# ind_pwm_gen.net
KiCad netlist of a schematic drawn in EAGLE
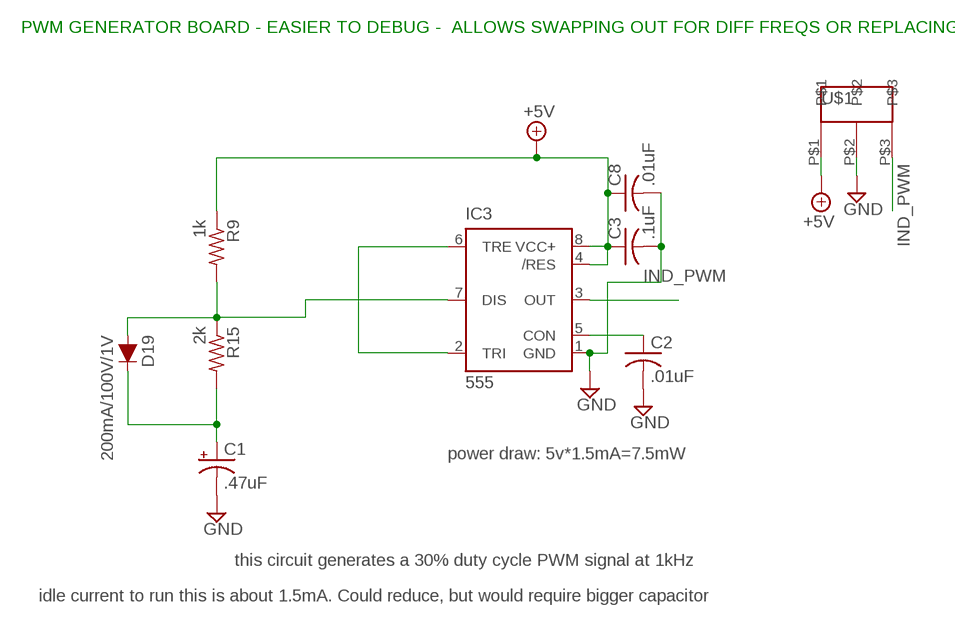
[diagram p0: schematic, sheet 1]

(export (version "E")
  (design (tool "Eeschema 10.0.6"))
  (components
    (comp (ref "C1")
      (value ".47uF")
      (footprint "eagle-import:E2-4")
      (libsource (lib "eagle-import") (part "CPOL-USE2-4"))
    )
    (comp (ref "C2")
      (value ".01uF")
      (footprint "eagle-import:C025-030X050")
      (libsource (lib "eagle-import") (part "C-US025-030X050"))
    )
    (comp (ref "C3")
      (value ".1uF")
      (footprint "eagle-import:C025-030X050")
      (libsource (lib "eagle-import") (part "C-US025-030X050"))
    )
    (comp (ref "C8")
      (value ".01uF")
      (footprint "eagle-import:C025-030X050")
      (libsource (lib "eagle-import") (part "C-US025-030X050"))
    )
    (comp (ref "D19")
      (value "200mA/100V/1V")
      (footprint "eagle-import:DIODE-1N4148")
      (libsource (lib "eagle-import") (part "DIODE-1N4148"))
    )
    (comp (ref "IC3")
      (value "555")
      (footprint "eagle-import:DIP08")
      (libsource (lib "eagle-import") (part "555P"))
    )
    (comp (ref "R9")
      (value "1k")
      (footprint "eagle-import:0204_7")
      (libsource (lib "eagle-import") (part "R-US_0204/7"))
    )
    (comp (ref "R15")
      (value "2k")
      (footprint "eagle-import:0204_7")
      (libsource (lib "eagle-import") (part "R-US_0204/7"))
    )
    (comp (ref "U$1")
      (value "3-PIN-HEADER")
      (footprint "eagle-import:3-PIN-HEADER")
      (libsource (lib "eagle-import") (part "3-PIN-HEADER"))
    )
  )
  (nets
    (net (code "1") (name "+5V") (class "Default")
      (node (ref "C3") (pin "1") (pinfunction "1_1") (pintype "passive"))
      (node (ref "C8") (pin "1") (pinfunction "1_1") (pintype "passive"))
      (node (ref "IC3") (pin "4") (pinfunction "/RES_4") (pintype "input"))
      (node (ref "IC3") (pin "8") (pinfunction "VCC+_8") (pintype "power_in"))
      (node (ref "R9") (pin "1") (pinfunction "1_1") (pintype "passive"))
      (node (ref "U$1") (pin "P$1") (pinfunction "P$1_P$1") (pintype "bidirectional"))
    )
    (net (code "2") (name "/IND_PWM") (class "Default")
      (node (ref "IC3") (pin "3") (pinfunction "OUT_3") (pintype "output"))
      (node (ref "U$1") (pin "P$3") (pinfunction "P$3_P$3") (pintype "bidirectional"))
    )
    (net (code "3") (name "GND") (class "Default")
      (node (ref "C1") (pin "-") (pinfunction "-_-") (pintype "passive"))
      (node (ref "C2") (pin "2") (pinfunction "2_2") (pintype "passive"))
      (node (ref "C3") (pin "2") (pinfunction "2_2") (pintype "passive"))
      (node (ref "C8") (pin "2") (pinfunction "2_2") (pintype "passive"))
      (node (ref "IC3") (pin "1") (pinfunction "GND_1") (pintype "power_in"))
      (node (ref "U$1") (pin "P$2") (pinfunction "P$2_P$2") (pintype "bidirectional"))
    )
    (net (code "4") (name "Net-(C1-Pad+)") (class "Default")
      (node (ref "C1") (pin "+") (pinfunction "+_+") (pintype "passive"))
      (node (ref "D19") (pin "C") (pinfunction "C_C") (pintype "passive"))
      (node (ref "R15") (pin "2") (pinfunction "2_2") (pintype "passive"))
    )
    (net (code "5") (name "Net-(IC3-CON)") (class "Default")
      (node (ref "C2") (pin "1") (pinfunction "1_1") (pintype "passive"))
      (node (ref "IC3") (pin "5") (pinfunction "CON_5") (pintype "input"))
    )
    (net (code "6") (name "Net-(IC3-DIS)") (class "Default")
      (node (ref "D19") (pin "A") (pinfunction "A_A") (pintype "passive"))
      (node (ref "IC3") (pin "7") (pinfunction "DIS_7") (pintype "input"))
      (node (ref "R15") (pin "1") (pinfunction "1_1") (pintype "passive"))
      (node (ref "R9") (pin "2") (pinfunction "2_2") (pintype "passive"))
    )
    (net (code "7") (name "Net-(IC3-TRE)") (class "Default")
      (node (ref "IC3") (pin "2") (pinfunction "TRI_2") (pintype "input"))
      (node (ref "IC3") (pin "6") (pinfunction "TRE_6") (pintype "input"))
    )
  )
)
